# MZQ-X99-SOLAR-20240924.net
KiCad netlist of a schematic drawn in Altium Designer
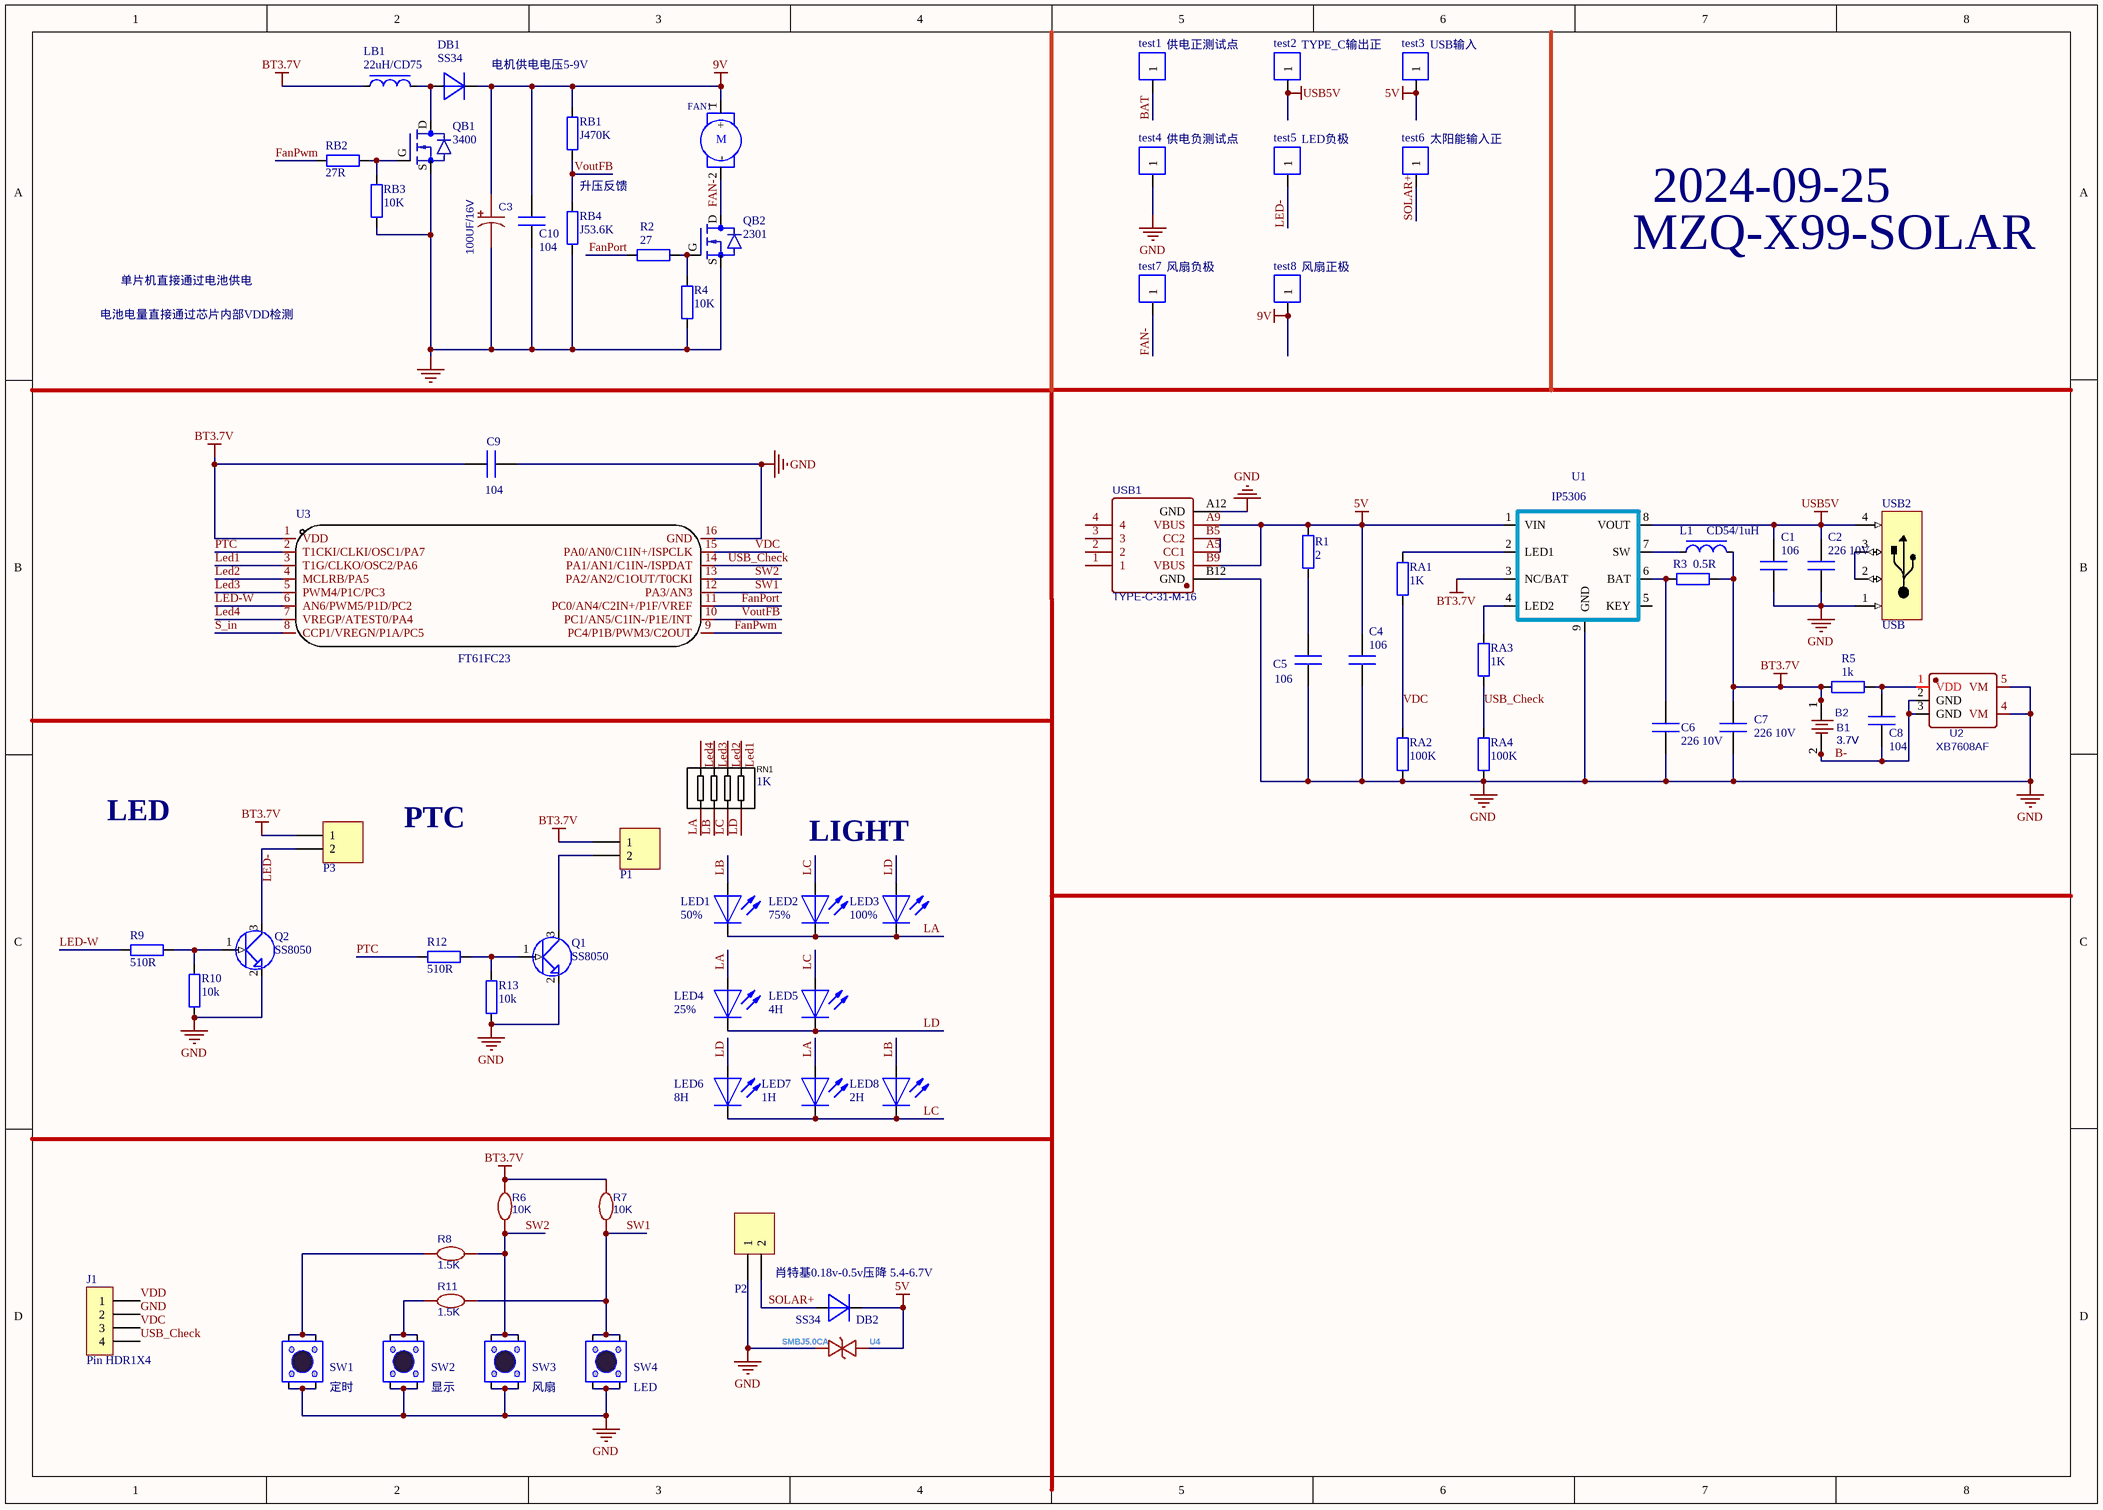
[diagram p0: MZQ-X99-SOLAR-20240924.SchDoc]

(export (version "E")
  (design (tool "Eeschema 10.0.6"))
  (components
    (comp (ref "B1")
      (value "3.7V")
      (footprint "PH2.0W-2P")
      (fields (field (name "BOM_MANUFACTURER PART") "CR1220-2") (field (name "BOM_SUPPLIER PART") "C70381"))
      (libsource (lib "altium-import") (part "root_3_12V_"))
    )
    (comp (ref "B2")
      (value "3.7V")
      (footprint "PH2.0W-2P")
      (fields (field (name "BOM_MANUFACTURER PART") "CR1220-2") (field (name "BOM_SUPPLIER PART") "C70381"))
      (libsource (lib "altium-import") (part "root_3_12V_"))
    )
    (comp (ref "C1")
      (value "106")
      (footprint "0805_C")
      (libsource (lib "KENNED 原理图标准封装-20160624") (part "Cap"))
    )
    (comp (ref "C2")
      (value "226 10V")
      (footprint "0805_C")
      (libsource (lib "KENNED 原理图标准封装-20160624") (part "Cap"))
    )
    (comp (ref "C3")
      (value "100UF/16V")
      (footprint "DIP-EC2.5X6.3X11.2")
      (fields
        (field (name "BOM_SUPPLIER PART") "C365767")
        (field (name "BOM_MANUFACTURER PART") "RC050M4R7LO5*11TH-2A1E")
        (field (name "CONTRIBUTOR") "s-dawn")
      )
      (libsource (lib "altium-import") (part "root_0_220uF/35V_"))
    )
    (comp (ref "C4")
      (value "106")
      (footprint "0805_C")
      (libsource (lib "KENNED 原理图标准封装-20160624") (part "Cap"))
    )
    (comp (ref "C5")
      (value "106")
      (footprint "0805_C")
      (libsource (lib "KENNED 原理图标准封装-20160624") (part "Cap"))
    )
    (comp (ref "C6")
      (value "226 10V")
      (footprint "0805_C")
      (libsource (lib "KENNED 原理图标准封装-20160624") (part "Cap"))
    )
    (comp (ref "C7")
      (value "226 10V")
      (footprint "0805_C")
      (libsource (lib "KENNED 原理图标准封装-20160624") (part "Cap"))
    )
    (comp (ref "C8")
      (value "104")
      (footprint "0603_C")
      (libsource (lib "KENNED 原理图标准封装-20160624") (part "Cap"))
    )
    (comp (ref "C9")
      (value "104")
      (footprint "0805_C")
      (libsource (lib "KENNED 原理图标准封装-20180426") (part "Cap"))
    )
    (comp (ref "C10")
      (value "104")
      (footprint "0603_C")
      (libsource (lib "KENNED 原理图标准封装-20160624") (part "Cap"))
    )
    (comp (ref "DB1")
      (value "SS34")
      (footprint "SMA(DO-214AC)_S1")
      (libsource (lib "KENNED 原理图标准封装-20180426") (part "Diode"))
    )
    (comp (ref "DB2")
      (value "SS34")
      (footprint "SMA(DO-214AC)_S1")
      (libsource (lib "KENNED 原理图标准封装-20180426") (part "Diode"))
    )
    (comp (ref "FAN1") (value "~") (footprint "PH2.0W-2P") (libsource (lib "*") (part "MotorDC-P")))
    (comp (ref "J1")
      (value "Pin HDR1X4")
      (footprint "Pin HDR1X4/2.54mm-S")
      (libsource (lib "排针") (part "Pin HDR1X4"))
    )
    (comp (ref "L1")
      (value "CD54/1uH")
      (footprint "CD54")
      (libsource (lib "KENNED 原理图标准封装-20180426") (part "L Core"))
    )
    (comp (ref "LB1")
      (value "22uH/CD75")
      (footprint "CD75")
      (libsource (lib "KENNED 原理图标准封装-20180426") (part "L Core"))
    )
    (comp (ref "LED1")
      (value "50%")
      (footprint "0603_LED_S1")
      (libsource (lib "KENNED 原理图标准封装-20160624") (part "LED"))
    )
    (comp (ref "LED2")
      (value "75%")
      (footprint "0603_LED_S1")
      (libsource (lib "KENNED 原理图标准封装-20160624") (part "LED"))
    )
    (comp (ref "LED3")
      (value "100%")
      (footprint "0603_LED_S1")
      (libsource (lib "KENNED 原理图标准封装-20160624") (part "LED"))
    )
    (comp (ref "LED4")
      (value "25%")
      (footprint "0603_LED_S1")
      (libsource (lib "KENNED 原理图标准封装-20160624") (part "LED"))
    )
    (comp (ref "LED5")
      (value "4H")
      (footprint "0603_LED_S1")
      (libsource (lib "KENNED 原理图标准封装-20160624") (part "LED"))
    )
    (comp (ref "LED6")
      (value "8H")
      (footprint "0603_LED_S1")
      (libsource (lib "KENNED 原理图标准封装-20160624") (part "LED"))
    )
    (comp (ref "LED7")
      (value "1H")
      (footprint "0603_LED_S1")
      (libsource (lib "KENNED 原理图标准封装-20160624") (part "LED"))
    )
    (comp (ref "LED8")
      (value "2H")
      (footprint "0603_LED_S1")
      (libsource (lib "KENNED 原理图标准封装-20160624") (part "LED"))
    )
    (comp (ref "P1")
      (value "Header 2")
      (footprint "HP-2")
      (description "Header, 2-Pin")
      (fields (field (name "PUBLISHER") "Altium Limited"))
      (libsource (lib "") (part "Header 2_1"))
    )
    (comp (ref "P2")
      (value "Header 2")
      (footprint "HP-2")
      (description "Header, 2-Pin")
      (fields (field (name "PUBLISHER") "Altium Limited"))
      (libsource (lib "Safety-Others") (part "Header 2"))
    )
    (comp (ref "P3")
      (value "Header 2")
      (footprint "HP-2")
      (description "Header, 2-Pin")
      (fields (field (name "PUBLISHER") "Altium Limited"))
      (libsource (lib "") (part "Header 2_1"))
    )
    (comp (ref "Q1")
      (value "SS8050")
      (footprint "SOT-23(SOT-23-3)")
      (libsource (lib "KENNED 原理图标准封装-20180426") (part "NPN-(EBC如8050 )"))
    )
    (comp (ref "Q2")
      (value "SS8050")
      (footprint "SOT-23(SOT-23-3)")
      (libsource (lib "KENNED 原理图标准封装-20180426") (part "NPN-(EBC如8050 )"))
    )
    (comp (ref "QB1")
      (value "3400")
      (footprint "SOT-23(SOT-23-3)")
      (libsource (lib "KENNED 原理图标准封装-20180426") (part "N MOS"))
    )
    (comp (ref "QB2")
      (value "2301")
      (footprint "SOT-23(SOT-23-3)")
      (libsource (lib "KENNED 原理图标准封装-20180426") (part "N MOS"))
    )
    (comp (ref "R1")
      (value "2")
      (footprint "0805_R")
      (libsource (lib "KENNED 原理图标准封装-20160624") (part "Res"))
    )
    (comp (ref "R2") (value "27") (footprint "0603_R") (libsource (lib "*") (part "Res")))
    (comp (ref "R3")
      (value "0.5R")
      (footprint "0603_R")
      (libsource (lib "KENNED 原理图标准封装-20160624") (part "Res"))
    )
    (comp (ref "R4") (value "10K") (footprint "0603_R") (libsource (lib "*") (part "Res")))
    (comp (ref "R5")
      (value "1k")
      (footprint "0603_R")
      (libsource (lib "KENNED 原理图标准封装-20160624") (part "Res"))
    )
    (comp (ref "R6")
      (value "10K")
      (footprint "0603_R")
      (fields (field (name "CONTRIBUTOR") "LCEDA_Lib"))
      (libsource (lib "altium-import") (part "root_3_1k_"))
    )
    (comp (ref "R7")
      (value "10K")
      (footprint "0603_R")
      (fields (field (name "CONTRIBUTOR") "LCEDA_Lib"))
      (libsource (lib "altium-import") (part "root_3_1k_"))
    )
    (comp (ref "R8")
      (value "1.5K")
      (footprint "0603_R")
      (fields (field (name "CONTRIBUTOR") "LCEDA_Lib"))
      (libsource (lib "altium-import") (part "root_0_1k_"))
    )
    (comp (ref "R9") (value "510R") (footprint "0603_R") (libsource (lib "*") (part "Res")))
    (comp (ref "R10") (value "10k") (footprint "0603_R") (libsource (lib "*") (part "Res")))
    (comp (ref "R11")
      (value "1.5K")
      (footprint "0603_R")
      (fields (field (name "CONTRIBUTOR") "LCEDA_Lib"))
      (libsource (lib "altium-import") (part "root_0_1k_"))
    )
    (comp (ref "R12") (value "510R") (footprint "0603_R") (libsource (lib "*") (part "Res")))
    (comp (ref "R13") (value "10k") (footprint "0603_R") (libsource (lib "*") (part "Res")))
    (comp (ref "RA1") (value "1K") (footprint "0603_R") (libsource (lib "*") (part "Res")))
    (comp (ref "RA2") (value "100K") (footprint "0603_R") (libsource (lib "*") (part "Res")))
    (comp (ref "RA3") (value "1K") (footprint "0603_R") (libsource (lib "*") (part "Res")))
    (comp (ref "RA4") (value "100K") (footprint "0603_R") (libsource (lib "*") (part "Res")))
    (comp (ref "RB1") (value "J470K") (footprint "0603_R") (libsource (lib "*") (part "Res")))
    (comp (ref "RB2") (value "27R") (footprint "0603_R") (libsource (lib "*") (part "Res")))
    (comp (ref "RB3") (value "10K") (footprint "0603_R") (libsource (lib "*") (part "Res")))
    (comp (ref "RB4") (value "J53.6K") (footprint "0603_R") (libsource (lib "*") (part "Res")))
    (comp (ref "RN1")
      (value "1K")
      (footprint "排阻(最新)SMT0603*4")
      (fields (field (name "MANUFACTURER PART") "YC164-JR-070RL"))
      (libsource (lib "altium-import") (part "root_2_YC164-JR-070RL_"))
    )
    (comp (ref "SW1") (value "定时") (footprint "SMD-6X6X6") (libsource (lib "") (part "SW-4_2")))
    (comp (ref "SW2") (value "显示") (footprint "SMD-6X6X6") (libsource (lib "*") (part "SW-4")))
    (comp (ref "SW3") (value "风扇") (footprint "SMD-6X6X6") (libsource (lib "") (part "SW-4_2")))
    (comp (ref "SW4") (value "LED") (footprint "SMD-6X6X6") (libsource (lib "") (part "SW-4_1")))
    (comp (ref "test1")
      (value "供电正测试点")
      (footprint "test3.0_top")
      (libsource (lib "KENNED 原理图标准封装-2023-9-7") (part "1P"))
    )
    (comp (ref "test2")
      (value "TYPE_C输出正")
      (footprint "test3.0_top")
      (libsource (lib "KENNED 原理图标准封装-2023-9-7") (part "1P"))
    )
    (comp (ref "test3")
      (value "USB输入")
      (footprint "test3.0_top")
      (libsource (lib "KENNED 原理图标准封装-2023-9-7") (part "1P"))
    )
    (comp (ref "test4")
      (value "供电负测试点")
      (footprint "test3.0_top")
      (libsource (lib "KENNED 原理图标准封装-2023-9-7") (part "1P"))
    )
    (comp (ref "test5")
      (value "LED负极")
      (footprint "test3.0_top")
      (libsource (lib "KENNED 原理图标准封装-2023-9-7") (part "1P"))
    )
    (comp (ref "test6")
      (value "太阳能输入正")
      (footprint "test3.0_top")
      (libsource (lib "KENNED 原理图标准封装-2023-9-7") (part "1P"))
    )
    (comp (ref "test7")
      (value "风扇负极")
      (footprint "test3.0_top")
      (libsource (lib "KENNED 原理图标准封装-2023-9-7") (part "1P"))
    )
    (comp (ref "test8")
      (value "风扇正极")
      (footprint "test3.0_top")
      (libsource (lib "KENNED 原理图标准封装-2023-9-7") (part "1P"))
    )
    (comp (ref "U1")
      (value "IP5306")
      (footprint "SOP-8_EP_150mil")
      (libsource (lib "黄植富") (part "IC-IP5303"))
    )
    (comp (ref "U2")
      (value "XB7608AF")
      (footprint "SOT-23-5")
      (fields (field (name "BOM_SUPPLIER PART") "C249345") (field (name "CONTRIBUTOR") "LCSC"))
      (libsource (lib "altium-import") (part "root_0_XB7608AF_"))
    )
    (comp (ref "U3")
      (value "FT61FC23")
      (footprint "SOIC-16_150mil")
      (fields (field (name "MANUFACTURER PART") "FT61FC23-RB"))
      (libsource (lib "altium-import") (part "root_0_FT61FC23-RB_"))
    )
    (comp (ref "U4")
      (value "SMBJ5.0CA")
      (footprint "SMB_L4.5-W3.6-LS5.2-BI")
      (fields (field (name "MANUFACTURER") "宏迦橙"))
      (libsource (lib "altium-import") (part "root_0_SMBJ5.0CA_C19077559_"))
    )
    (comp (ref "USB1")
      (value "TYPE-C-31-M-16")
      (footprint "USB-C-6")
      (fields (field (name "BOM_SUPPLIER PART") "C283541") (field (name "CONTRIBUTOR") "LCSC"))
      (libsource (lib "altium-import") (part "root_2_TYPE-C-31-M-16_"))
    )
    (comp (ref "USB2") (value "USB") (footprint "MI-USB-90") (libsource (lib "*") (part "USB")))
  )
  (nets
    (net (code "1") (name "/B-") (class "Default")
      (node (ref "B1") (pin "2") (pinfunction "2_2") (pintype "passive"))
      (node (ref "B2") (pin "2") (pinfunction "2_2") (pintype "passive"))
      (node (ref "C8") (pin "1") (pinfunction "1_1") (pintype "passive"))
      (node (ref "U2") (pin "2") (pinfunction "GND_2") (pintype "passive"))
      (node (ref "U2") (pin "3") (pinfunction "GND_3") (pintype "passive"))
    )
    (net (code "2") (name "/BAT") (class "Default")
      (node (ref "test1") (pin "1") (pinfunction "1_1") (pintype "passive"))
    )
    (net (code "3") (name "/FAN-") (class "Default")
      (node (ref "FAN1") (pin "2") (pinfunction "-_2") (pintype "passive"))
      (node (ref "QB2") (pin "2") (pinfunction "G_2") (pintype "passive"))
      (node (ref "test7") (pin "1") (pinfunction "1_1") (pintype "passive"))
    )
    (net (code "4") (name "/FanPort") (class "Default")
      (node (ref "R2") (pin "2") (pinfunction "2_2") (pintype "passive"))
      (node (ref "U3") (pin "11") (pinfunction "PC0/AN4/C2IN+/P1F/VREF_11") (pintype "passive"))
    )
    (net (code "5") (name "/FanPwm") (class "Default")
      (node (ref "RB2") (pin "1") (pinfunction "1_1") (pintype "passive"))
      (node (ref "U3") (pin "9") (pinfunction "PC4/P1B/PWM3/C2OUT_9") (pintype "passive"))
    )
    (net (code "6") (name "/LA") (class "Default")
      (node (ref "LED1") (pin "2") (pinfunction "2_2") (pintype "passive"))
      (node (ref "LED2") (pin "2") (pinfunction "2_2") (pintype "passive"))
      (node (ref "LED3") (pin "2") (pinfunction "2_2") (pintype "passive"))
      (node (ref "LED4") (pin "1") (pinfunction "1_1") (pintype "passive"))
      (node (ref "LED7") (pin "1") (pinfunction "1_1") (pintype "passive"))
      (node (ref "RN1") (pin "5") (pinfunction "5_5") (pintype "passive"))
    )
    (net (code "7") (name "/LB") (class "Default")
      (node (ref "LED1") (pin "1") (pinfunction "1_1") (pintype "passive"))
      (node (ref "LED8") (pin "1") (pinfunction "1_1") (pintype "passive"))
      (node (ref "RN1") (pin "6") (pinfunction "6_6") (pintype "passive"))
    )
    (net (code "8") (name "/LC") (class "Default")
      (node (ref "LED2") (pin "1") (pinfunction "1_1") (pintype "passive"))
      (node (ref "LED5") (pin "1") (pinfunction "1_1") (pintype "passive"))
      (node (ref "LED6") (pin "2") (pinfunction "2_2") (pintype "passive"))
      (node (ref "LED7") (pin "2") (pinfunction "2_2") (pintype "passive"))
      (node (ref "LED8") (pin "2") (pinfunction "2_2") (pintype "passive"))
      (node (ref "RN1") (pin "7") (pinfunction "7_7") (pintype "passive"))
    )
    (net (code "9") (name "/LD") (class "Default")
      (node (ref "LED3") (pin "1") (pinfunction "1_1") (pintype "passive"))
      (node (ref "LED4") (pin "2") (pinfunction "2_2") (pintype "passive"))
      (node (ref "LED5") (pin "2") (pinfunction "2_2") (pintype "passive"))
      (node (ref "LED6") (pin "1") (pinfunction "1_1") (pintype "passive"))
      (node (ref "RN1") (pin "8") (pinfunction "8_8") (pintype "passive"))
    )
    (net (code "10") (name "/LED-") (class "Default")
      (node (ref "test5") (pin "1") (pinfunction "1_1") (pintype "passive"))
    )
    (net (code "11") (name "/LED-W") (class "Default")
      (node (ref "R9") (pin "1") (pinfunction "1_1") (pintype "passive"))
      (node (ref "U3") (pin "6") (pinfunction "AN6/PWM5/P1D/PC2_6") (pintype "passive"))
    )
    (net (code "12") (name "/Led1") (class "Default")
      (node (ref "RN1") (pin "1") (pinfunction "1_1") (pintype "passive"))
      (node (ref "U3") (pin "3") (pinfunction "T1G/CLKO/OSC2/PA6_3") (pintype "passive"))
    )
    (net (code "13") (name "/Led2") (class "Default")
      (node (ref "RN1") (pin "2") (pinfunction "2_2") (pintype "passive"))
      (node (ref "U3") (pin "4") (pinfunction "MCLRB/PA5_4") (pintype "passive"))
    )
    (net (code "14") (name "/Led3") (class "Default")
      (node (ref "RN1") (pin "3") (pinfunction "3_3") (pintype "passive"))
      (node (ref "U3") (pin "5") (pinfunction "PWM4/P1C/PC3_5") (pintype "passive"))
    )
    (net (code "15") (name "/Led4") (class "Default")
      (node (ref "RN1") (pin "4") (pinfunction "4_4") (pintype "passive"))
      (node (ref "U3") (pin "7") (pinfunction "VREGP/ATEST0/PA4_7") (pintype "passive"))
    )
    (net (code "16") (name "/PTC") (class "Default")
      (node (ref "R12") (pin "1") (pinfunction "1_1") (pintype "passive"))
      (node (ref "U3") (pin "2") (pinfunction "T1CKI/CLKI/OSC1/PA7_2") (pintype "passive"))
    )
    (net (code "17") (name "/SOLAR+") (class "Default")
      (node (ref "DB2") (pin "1") (pinfunction "1_1") (pintype "passive"))
      (node (ref "P2") (pin "2") (pinfunction "2_2") (pintype "passive"))
      (node (ref "test6") (pin "1") (pinfunction "1_1") (pintype "passive"))
    )
    (net (code "18") (name "/SW1") (class "Default")
      (node (ref "R11") (pin "2") (pinfunction "2_2") (pintype "passive"))
      (node (ref "R7") (pin "2") (pinfunction "2_2") (pintype "passive"))
      (node (ref "SW4") (pin "2") (pintype "passive"))
      (node (ref "SW4") (pin "4") (pintype "passive"))
      (node (ref "U3") (pin "12") (pinfunction "PA3/AN3_12") (pintype "passive"))
    )
    (net (code "19") (name "/SW2") (class "Default")
      (node (ref "R6") (pin "2") (pinfunction "2_2") (pintype "passive"))
      (node (ref "R8") (pin "2") (pinfunction "2_2") (pintype "passive"))
      (node (ref "SW3") (pin "2") (pintype "passive"))
      (node (ref "SW3") (pin "4") (pintype "passive"))
      (node (ref "U3") (pin "13") (pinfunction "PA2/AN2/C1OUT/T0CKI_13") (pintype "passive"))
    )
    (net (code "20") (name "/S_in") (class "Default")
      (node (ref "U3") (pin "8") (pinfunction "CCP1/VREGN/P1A/PC5_8") (pintype "passive"))
    )
    (net (code "21") (name "/USB_Check") (class "Default")
      (node (ref "J1") (pin "4") (pinfunction "4_4") (pintype "passive"))
      (node (ref "RA3") (pin "1") (pinfunction "1_1") (pintype "passive"))
      (node (ref "RA4") (pin "2") (pinfunction "2_2") (pintype "passive"))
      (node (ref "U3") (pin "14") (pinfunction "PA1/AN1/C1IN-/ISPDAT_14") (pintype "passive"))
    )
    (net (code "22") (name "/VDC") (class "Default")
      (node (ref "J1") (pin "3") (pinfunction "3_3") (pintype "passive"))
      (node (ref "RA1") (pin "1") (pinfunction "1_1") (pintype "passive"))
      (node (ref "RA2") (pin "2") (pinfunction "2_2") (pintype "passive"))
      (node (ref "U3") (pin "15") (pinfunction "PA0/AN0/C1IN+/ISPCLK_15") (pintype "passive"))
    )
    (net (code "23") (name "/VDD") (class "Default")
      (node (ref "J1") (pin "1") (pinfunction "1_1") (pintype "passive"))
    )
    (net (code "24") (name "/VoutFB") (class "Default")
      (node (ref "RB1") (pin "1") (pinfunction "1_1") (pintype "passive"))
      (node (ref "RB4") (pin "2") (pinfunction "2_2") (pintype "passive"))
      (node (ref "U3") (pin "10") (pinfunction "PC1/AN5/C1IN-/P1E/INT_10") (pintype "passive"))
    )
    (net (code "25") (name "5V") (class "Default")
      (node (ref "C4") (pin "2") (pinfunction "2_2") (pintype "passive"))
      (node (ref "DB2") (pin "2") (pinfunction "2_2") (pintype "passive"))
      (node (ref "R1") (pin "2") (pinfunction "2_2") (pintype "passive"))
      (node (ref "U1") (pin "1") (pinfunction "VIN_1") (pintype "passive"))
      (node (ref "U4") (pin "2") (pinfunction "2_2") (pintype "passive"))
      (node (ref "USB1") (pin "A9") (pinfunction "VBUS_A9") (pintype "passive"))
      (node (ref "USB1") (pin "B9") (pinfunction "VBUS_B9") (pintype "passive"))
      (node (ref "test3") (pin "1") (pinfunction "1_1") (pintype "passive"))
    )
    (net (code "26") (name "9V") (class "Default")
      (node (ref "C10") (pin "2") (pinfunction "2_2") (pintype "passive"))
      (node (ref "C3") (pin "1") (pinfunction "1_1") (pintype "passive"))
      (node (ref "DB1") (pin "2") (pinfunction "2_2") (pintype "passive"))
      (node (ref "FAN1") (pin "1") (pinfunction "+_1") (pintype "passive"))
      (node (ref "RB1") (pin "2") (pinfunction "2_2") (pintype "passive"))
      (node (ref "test8") (pin "1") (pinfunction "1_1") (pintype "passive"))
    )
    (net (code "27") (name "BT3.7V") (class "Default")
      (node (ref "B1") (pin "1") (pinfunction "1_1") (pintype "passive"))
      (node (ref "B2") (pin "1") (pinfunction "1_1") (pintype "passive"))
      (node (ref "C7") (pin "2") (pinfunction "2_2") (pintype "passive"))
      (node (ref "C9") (pin "2") (pinfunction "2_2") (pintype "passive"))
      (node (ref "L1") (pin "2") (pinfunction "2_2") (pintype "passive"))
      (node (ref "LB1") (pin "1") (pinfunction "1_1") (pintype "passive"))
      (node (ref "P1") (pin "1") (pinfunction "1_1") (pintype "passive"))
      (node (ref "P3") (pin "1") (pinfunction "1_1") (pintype "passive"))
      (node (ref "R3") (pin "1") (pinfunction "1_1") (pintype "passive"))
      (node (ref "R5") (pin "2") (pinfunction "2_2") (pintype "passive"))
      (node (ref "R6") (pin "1") (pinfunction "1_1") (pintype "passive"))
      (node (ref "R7") (pin "1") (pinfunction "1_1") (pintype "passive"))
      (node (ref "U1") (pin "3") (pinfunction "NC/BAT_3") (pintype "passive"))
      (node (ref "U3") (pin "1") (pinfunction "VDD_1") (pintype "passive"))
    )
    (net (code "28") (name "GND") (class "Default")
      (node (ref "C1") (pin "1") (pinfunction "1_1") (pintype "passive"))
      (node (ref "C10") (pin "1") (pinfunction "1_1") (pintype "passive"))
      (node (ref "C2") (pin "1") (pinfunction "1_1") (pintype "passive"))
      (node (ref "C3") (pin "2") (pinfunction "2_2") (pintype "passive"))
      (node (ref "C4") (pin "1") (pinfunction "1_1") (pintype "passive"))
      (node (ref "C5") (pin "1") (pinfunction "1_1") (pintype "passive"))
      (node (ref "C6") (pin "2") (pinfunction "2_2") (pintype "passive"))
      (node (ref "C7") (pin "1") (pinfunction "1_1") (pintype "passive"))
      (node (ref "C9") (pin "1") (pinfunction "1_1") (pintype "passive"))
      (node (ref "J1") (pin "2") (pinfunction "2_2") (pintype "passive"))
      (node (ref "P2") (pin "1") (pinfunction "1_1") (pintype "passive"))
      (node (ref "Q1") (pin "2") (pinfunction "E_2") (pintype "passive"))
      (node (ref "Q2") (pin "2") (pinfunction "E_2") (pintype "passive"))
      (node (ref "QB1") (pin "3") (pinfunction "S_3") (pintype "passive"))
      (node (ref "QB2") (pin "3") (pinfunction "S_3") (pintype "passive"))
      (node (ref "R10") (pin "1") (pinfunction "1_1") (pintype "passive"))
      (node (ref "R13") (pin "1") (pinfunction "1_1") (pintype "passive"))
      (node (ref "R4") (pin "1") (pinfunction "1_1") (pintype "passive"))
      (node (ref "RA2") (pin "1") (pinfunction "1_1") (pintype "passive"))
      (node (ref "RA4") (pin "1") (pinfunction "1_1") (pintype "passive"))
      (node (ref "RB3") (pin "1") (pinfunction "1_1") (pintype "passive"))
      (node (ref "RB4") (pin "1") (pinfunction "1_1") (pintype "passive"))
      (node (ref "SW1") (pin "1") (pintype "passive"))
      (node (ref "SW1") (pin "3") (pintype "passive"))
      (node (ref "SW2") (pin "1") (pintype "passive"))
      (node (ref "SW2") (pin "3") (pintype "passive"))
      (node (ref "SW3") (pin "1") (pintype "passive"))
      (node (ref "SW3") (pin "3") (pintype "passive"))
      (node (ref "SW4") (pin "1") (pintype "passive"))
      (node (ref "SW4") (pin "3") (pintype "passive"))
      (node (ref "U1") (pin "9") (pinfunction "GND_9") (pintype "passive"))
      (node (ref "U2") (pin "4") (pinfunction "VM_4") (pintype "passive"))
      (node (ref "U2") (pin "5") (pinfunction "VM_5") (pintype "passive"))
      (node (ref "U3") (pin "16") (pinfunction "GND_16") (pintype "passive"))
      (node (ref "U4") (pin "1") (pinfunction "1_1") (pintype "passive"))
      (node (ref "USB1") (pin "A12") (pinfunction "GND_A12") (pintype "passive"))
      (node (ref "USB1") (pin "B12") (pinfunction "GND_B12") (pintype "passive"))
      (node (ref "USB2") (pin "1") (pinfunction "1_1") (pintype "input"))
      (node (ref "test4") (pin "1") (pinfunction "1_1") (pintype "passive"))
    )
    (net (code "29") (name "Net-(C5-Pad2)") (class "Default")
      (node (ref "C5") (pin "2") (pinfunction "2_2") (pintype "passive"))
      (node (ref "R1") (pin "1") (pinfunction "1_1") (pintype "passive"))
    )
    (net (code "30") (name "Net-(DB1-Pad1)") (class "Default")
      (node (ref "DB1") (pin "1") (pinfunction "1_1") (pintype "passive"))
      (node (ref "LB1") (pin "2") (pinfunction "2_2") (pintype "passive"))
      (node (ref "QB1") (pin "2") (pinfunction "G_2") (pintype "passive"))
    )
    (net (code "31") (name "Net-(Q1-B)") (class "Default")
      (node (ref "Q1") (pin "1") (pinfunction "B_1") (pintype "input"))
      (node (ref "R12") (pin "2") (pinfunction "2_2") (pintype "passive"))
      (node (ref "R13") (pin "2") (pinfunction "2_2") (pintype "passive"))
    )
    (net (code "32") (name "Net-(Q1-C)") (class "Default")
      (node (ref "P1") (pin "2") (pinfunction "2_2") (pintype "passive"))
      (node (ref "Q1") (pin "3") (pinfunction "C_3") (pintype "passive"))
    )
    (net (code "33") (name "Net-(Q2-B)") (class "Default")
      (node (ref "Q2") (pin "1") (pinfunction "B_1") (pintype "input"))
      (node (ref "R10") (pin "2") (pinfunction "2_2") (pintype "passive"))
      (node (ref "R9") (pin "2") (pinfunction "2_2") (pintype "passive"))
    )
    (net (code "34") (name "Net-(Q2-C)") (class "Default")
      (node (ref "P3") (pin "2") (pinfunction "2_2") (pintype "passive"))
      (node (ref "Q2") (pin "3") (pinfunction "C_3") (pintype "passive"))
    )
    (net (code "35") (name "Net-(QB1-G-Pad1)") (class "Default")
      (node (ref "QB1") (pin "1") (pinfunction "G_1") (pintype "passive"))
      (node (ref "RB2") (pin "2") (pinfunction "2_2") (pintype "passive"))
      (node (ref "RB3") (pin "2") (pinfunction "2_2") (pintype "passive"))
    )
    (net (code "36") (name "Net-(QB2-G-Pad1)") (class "Default")
      (node (ref "QB2") (pin "1") (pinfunction "G_1") (pintype "passive"))
      (node (ref "R2") (pin "1") (pinfunction "1_1") (pintype "passive"))
      (node (ref "R4") (pin "2") (pinfunction "2_2") (pintype "passive"))
    )
    (net (code "37") (name "Net-(R8-Pad1)") (class "Default")
      (node (ref "R8") (pin "1") (pinfunction "1_1") (pintype "passive"))
      (node (ref "SW1") (pin "2") (pintype "passive"))
      (node (ref "SW1") (pin "4") (pintype "passive"))
    )
    (net (code "38") (name "Net-(R11-Pad1)") (class "Default")
      (node (ref "R11") (pin "1") (pinfunction "1_1") (pintype "passive"))
      (node (ref "SW2") (pin "2") (pintype "passive"))
      (node (ref "SW2") (pin "4") (pintype "passive"))
    )
    (net (code "39") (name "Net-(U1-BAT)") (class "Default")
      (node (ref "C6") (pin "1") (pinfunction "1_1") (pintype "passive"))
      (node (ref "R3") (pin "2") (pinfunction "2_2") (pintype "passive"))
      (node (ref "U1") (pin "6") (pinfunction "BAT_6") (pintype "passive"))
    )
    (net (code "40") (name "Net-(U1-LED1)") (class "Default")
      (node (ref "RA1") (pin "2") (pinfunction "2_2") (pintype "passive"))
      (node (ref "U1") (pin "2") (pinfunction "LED1_2") (pintype "passive"))
    )
    (net (code "41") (name "Net-(U1-LED2)") (class "Default")
      (node (ref "RA3") (pin "2") (pinfunction "2_2") (pintype "passive"))
      (node (ref "U1") (pin "4") (pinfunction "LED2_4") (pintype "passive"))
    )
    (net (code "42") (name "Net-(U1-SW)") (class "Default")
      (node (ref "L1") (pin "1") (pinfunction "1_1") (pintype "passive"))
      (node (ref "U1") (pin "7") (pinfunction "SW_7") (pintype "passive"))
    )
    (net (code "43") (name "Net-(U2-VDD)") (class "Default")
      (node (ref "C8") (pin "2") (pinfunction "2_2") (pintype "passive"))
      (node (ref "R5") (pin "1") (pinfunction "1_1") (pintype "passive"))
      (node (ref "U2") (pin "1") (pinfunction "VDD_1") (pintype "passive"))
    )
    (net (code "44") (name "Net-(USB1-CC1)") (class "Default")
      (node (ref "USB1") (pin "A5") (pinfunction "CC1_A5") (pintype "passive"))
      (node (ref "USB1") (pin "B5") (pinfunction "CC2_B5") (pintype "passive"))
    )
    (net (code "45") (name "Net-(USB2-Pad2)") (class "Default")
      (node (ref "USB2") (pin "2") (pinfunction "2_2") (pintype "bidirectional"))
      (node (ref "USB2") (pin "3") (pinfunction "3_3") (pintype "bidirectional"))
    )
    (net (code "46") (name "USB5V") (class "Default")
      (node (ref "C1") (pin "2") (pinfunction "2_2") (pintype "passive"))
      (node (ref "C2") (pin "2") (pinfunction "2_2") (pintype "passive"))
      (node (ref "U1") (pin "8") (pinfunction "VOUT_8") (pintype "passive"))
      (node (ref "USB2") (pin "4") (pinfunction "4_4") (pintype "input"))
      (node (ref "test2") (pin "1") (pinfunction "1_1") (pintype "passive"))
    )
    (net (code "47") (name "unconnected-(U1-KEY-Pad5)") (class "Default")
      (node (ref "U1") (pin "5") (pinfunction "KEY_5") (pintype "passive"))
    )
    (net (code "48") (name "unconnected-(USB1-Pad1)") (class "Default")
      (node (ref "USB1") (pin "1") (pinfunction "1_1") (pintype "passive"))
    )
    (net (code "49") (name "unconnected-(USB1-Pad2)") (class "Default")
      (node (ref "USB1") (pin "2") (pinfunction "2_2") (pintype "passive"))
    )
    (net (code "50") (name "unconnected-(USB1-Pad3)") (class "Default")
      (node (ref "USB1") (pin "3") (pinfunction "3_3") (pintype "passive"))
    )
    (net (code "51") (name "unconnected-(USB1-Pad4)") (class "Default")
      (node (ref "USB1") (pin "4") (pinfunction "4_4") (pintype "passive"))
    )
  )
)
